# Current_Sensor.net
KiCad netlist of a schematic drawn in EAGLE
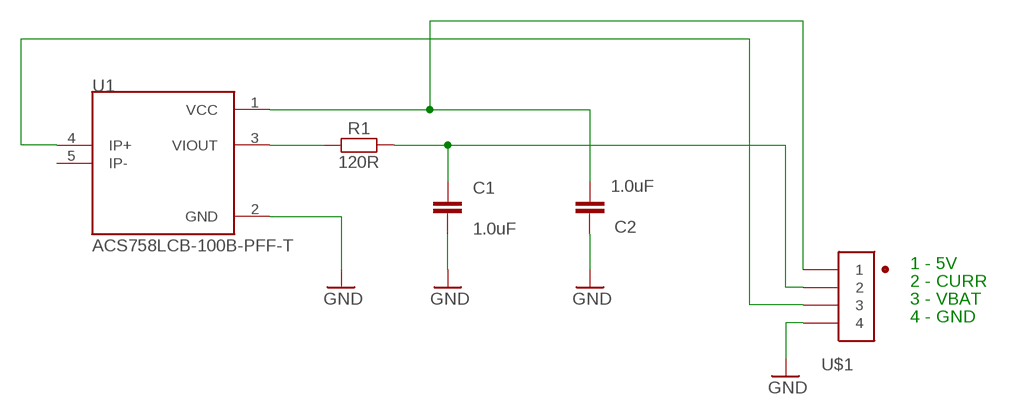
[diagram p0: schematic, sheet 1]

(export (version "E")
  (design (tool "Eeschema 10.0.6"))
  (components
    (comp (ref "C1")
      (value "1.0uF")
      (footprint "eagle-import:0603")
      (libsource (lib "eagle-import") (part "1.0UF-0603-16V-10%"))
    )
    (comp (ref "C2")
      (value "1.0uF")
      (footprint "eagle-import:0603")
      (libsource (lib "eagle-import") (part "1.0UF-0603-16V-10%"))
    )
    (comp (ref "R1")
      (value "120R")
      (footprint "eagle-import:0603")
      (libsource (lib "eagle-import") (part "RESISTOR0603"))
    )
    (comp (ref "U$1")
      (value "JST-SH-4PINJST-SH-4-HORIZONTAL")
      (footprint "eagle-import:JST-SH-4PIN-1.0MM")
      (libsource (lib "eagle-import") (part "JST-SH-4PINJST-SH-4-HORIZONTAL"))
    )
    (comp (ref "U1")
      (value "ACS758LCB-100B-PFF-T")
      (footprint "eagle-import:XDCR_ACS770KCB-150U-PFF-T")
      (fields (field (name "MF") "Allegro"))
      (libsource (lib "eagle-import") (part "ACS758LCB-100B-PFF-T"))
    )
  )
  (nets
    (net (code "1") (name "GND") (class "Default")
      (node (ref "C1") (pin "2") (pinfunction "2_2") (pintype "passive"))
      (node (ref "C2") (pin "1") (pinfunction "1_1") (pintype "passive"))
      (node (ref "U$1") (pin "4") (pinfunction "4_4") (pintype "bidirectional"))
      (node (ref "U1") (pin "2") (pinfunction "GND_2") (pintype "power_in"))
    )
    (net (code "2") (name "Net-(C1-Pad1)") (class "Default")
      (node (ref "C1") (pin "1") (pinfunction "1_1") (pintype "passive"))
      (node (ref "R1") (pin "2") (pinfunction "2_2") (pintype "passive"))
      (node (ref "U$1") (pin "2") (pinfunction "2_2") (pintype "bidirectional"))
    )
    (net (code "3") (name "Net-(U1-IP+)") (class "Default")
      (node (ref "U$1") (pin "3") (pinfunction "3_3") (pintype "bidirectional"))
      (node (ref "U1") (pin "4") (pinfunction "IP+_4") (pintype "input"))
    )
    (net (code "4") (name "Net-(U1-VCC)") (class "Default")
      (node (ref "C2") (pin "2") (pinfunction "2_2") (pintype "passive"))
      (node (ref "U$1") (pin "1") (pinfunction "1_1") (pintype "bidirectional"))
      (node (ref "U1") (pin "1") (pinfunction "VCC_1") (pintype "power_in"))
    )
    (net (code "5") (name "Net-(U1-VIOUT)") (class "Default")
      (node (ref "R1") (pin "1") (pinfunction "1_1") (pintype "passive"))
      (node (ref "U1") (pin "3") (pinfunction "VIOUT_3") (pintype "output"))
    )
    (net (code "6") (name "unconnected-(U1-IP--Pad5)") (class "Default")
      (node (ref "U1") (pin "5") (pinfunction "IP-_5") (pintype "input"))
    )
  )
)
